# ACE.net
KiCad netlist of a schematic drawn in Altium Designer
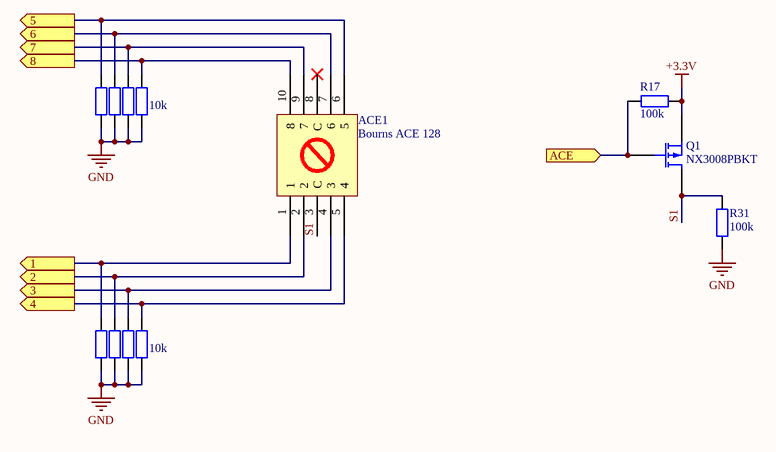
[diagram p0: ACE.SchDoc]

(export (version "E")
  (design (tool "Eeschema 10.0.6"))
  (components
    (comp (ref "ACE1")
      (value "Bourns ACE 128")
      (footprint "Bourns ACE 128")
      (libsource (lib "led_ring") (part "Bourns ACE 128"))
    )
    (comp (ref "Q1")
      (value "NX3008PBKT")
      (footprint "SOT95P230X110-3L")
      (description "P-Channel MOSFET")
      (fields (field (name "PUBLISHER") "Altium Limited"))
      (libsource (lib "Miscellaneous Devices") (part "MOSFET-P"))
    )
    (comp (ref "R17")
      (value "100k")
      (footprint "R1005_0402i_L")
      (description "R")
      (libsource (lib "General") (part "R"))
    )
    (comp (ref "R18")
      (value "10k")
      (footprint "R1005_0402i_L")
      (description "R")
      (libsource (lib "General") (part "R"))
    )
    (comp (ref "R19")
      (value "10k")
      (footprint "R1005_0402i_L")
      (description "R")
      (libsource (lib "General") (part "R"))
    )
    (comp (ref "R20")
      (value "10k")
      (footprint "R1005_0402i_L")
      (description "R")
      (libsource (lib "General") (part "R"))
    )
    (comp (ref "R21")
      (value "10k")
      (footprint "R1005_0402i_L")
      (description "R")
      (libsource (lib "General") (part "R"))
    )
    (comp (ref "R22")
      (value "10k")
      (footprint "R1005_0402i_L")
      (description "R")
      (libsource (lib "General") (part "R"))
    )
    (comp (ref "R23")
      (value "10k")
      (footprint "R1005_0402i_L")
      (description "R")
      (libsource (lib "General") (part "R"))
    )
    (comp (ref "R24")
      (value "10k")
      (footprint "R1005_0402i_L")
      (description "R")
      (libsource (lib "General") (part "R"))
    )
    (comp (ref "R25")
      (value "10k")
      (footprint "R1005_0402i_L")
      (description "R")
      (libsource (lib "General") (part "R"))
    )
    (comp (ref "R31")
      (value "100k")
      (footprint "R1005_0402i_L")
      (description "R")
      (libsource (lib "General") (part "R"))
    )
  )
  (nets
    (net (code "1") (name "+3.3V") (class "Default")
      (node (ref "Q1") (pin "2") (pinfunction "S_2") (pintype "passive"))
      (node (ref "R17") (pin "2") (pintype "passive"))
    )
    (net (code "2") (name "/1") (class "Default")
      (node (ref "ACE1") (pin "1") (pinfunction "1_1") (pintype "passive"))
      (node (ref "R22") (pin "2") (pintype "passive"))
    )
    (net (code "3") (name "/2") (class "Default")
      (node (ref "ACE1") (pin "2") (pinfunction "2_2") (pintype "passive"))
      (node (ref "R23") (pin "2") (pintype "passive"))
    )
    (net (code "4") (name "/3") (class "Default")
      (node (ref "ACE1") (pin "4") (pinfunction "3_4") (pintype "passive"))
      (node (ref "R24") (pin "2") (pintype "passive"))
    )
    (net (code "5") (name "/4") (class "Default")
      (node (ref "ACE1") (pin "5") (pinfunction "4_5") (pintype "passive"))
      (node (ref "R25") (pin "2") (pintype "passive"))
    )
    (net (code "6") (name "/5") (class "Default")
      (node (ref "ACE1") (pin "6") (pinfunction "5_6") (pintype "passive"))
      (node (ref "R18") (pin "2") (pintype "passive"))
    )
    (net (code "7") (name "/6") (class "Default")
      (node (ref "ACE1") (pin "7") (pinfunction "6_7") (pintype "passive"))
      (node (ref "R19") (pin "2") (pintype "passive"))
    )
    (net (code "8") (name "/7") (class "Default")
      (node (ref "ACE1") (pin "9") (pinfunction "7_9") (pintype "passive"))
      (node (ref "R20") (pin "2") (pintype "passive"))
    )
    (net (code "9") (name "/8") (class "Default")
      (node (ref "ACE1") (pin "10") (pinfunction "8_10") (pintype "passive"))
      (node (ref "R21") (pin "2") (pintype "passive"))
    )
    (net (code "10") (name "/ACE") (class "Default")
      (node (ref "Q1") (pin "1") (pinfunction "G_1") (pintype "passive"))
      (node (ref "R17") (pin "1") (pintype "passive"))
    )
    (net (code "11") (name "/S1") (class "Default")
      (node (ref "ACE1") (pin "3") (pinfunction "C_3") (pintype "passive"))
      (node (ref "Q1") (pin "3") (pinfunction "D_3") (pintype "passive"))
      (node (ref "R31") (pin "2") (pintype "passive"))
    )
    (net (code "12") (name "GND") (class "Default")
      (node (ref "R18") (pin "1") (pintype "passive"))
      (node (ref "R19") (pin "1") (pintype "passive"))
      (node (ref "R20") (pin "1") (pintype "passive"))
      (node (ref "R21") (pin "1") (pintype "passive"))
      (node (ref "R22") (pin "1") (pintype "passive"))
      (node (ref "R23") (pin "1") (pintype "passive"))
      (node (ref "R24") (pin "1") (pintype "passive"))
      (node (ref "R25") (pin "1") (pintype "passive"))
      (node (ref "R31") (pin "1") (pintype "passive"))
    )
    (net (code "13") (name "unconnected-(ACE1-C-Pad8)") (class "Default")
      (node (ref "ACE1") (pin "8") (pinfunction "C_8") (pintype "passive+no_connect"))
    )
  )
)
